# main.net
KiCad netlist of a schematic drawn in EAGLE
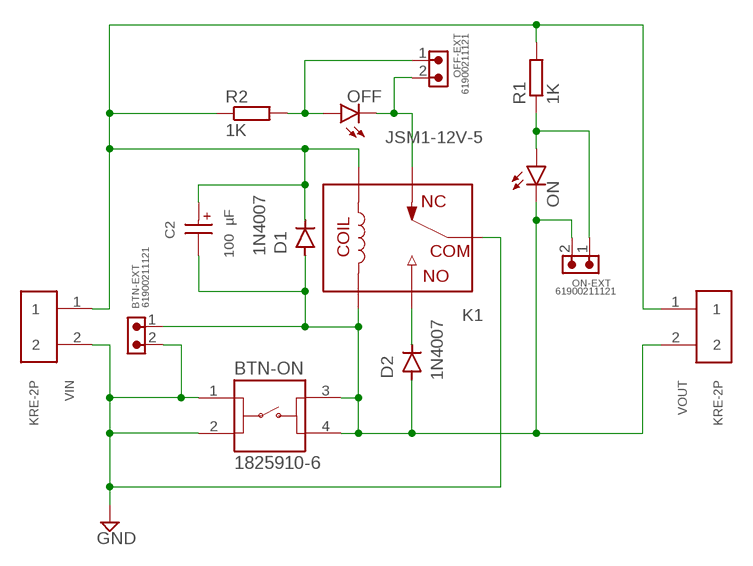
[diagram p0: schematic, sheet 1]

(export (version "E")
  (design (tool "Eeschema 10.0.6"))
  (components
    (comp (ref "BTN-EXT")
      (value "61900211121")
      (footprint "eagle-import:61900211121")
      (libsource (lib "eagle-import") (part "61900211121"))
    )
    (comp (ref "BTN-ON")
      (value "1825910-6")
      (footprint "eagle-import:1825910-6")
      (fields
        (field (name "DIGIKEY_PART_NUMBER") "450-1650-ND")
        (field (name "MANUFACTURER") "TE Connectivity ALCOSWITCH Switches")
        (field (name "CREATED_BY") " PCBLayout.com")
      )
      (libsource (lib "eagle-import") (part "1825910-6"))
    )
    (comp (ref "C2")
      (value "100 µF")
      (footprint "eagle-import:WCAP-ATLL_5X11(DXL)")
      (libsource (lib "eagle-import") (part "WCAP-ATLL_5X11_860160372011"))
    )
    (comp (ref "D1")
      (value "1N4007")
      (footprint "eagle-import:DO-41")
      (fields
        (field (name "DIGIKEY_PART_NUMBER") "1N4007MSCT-ND")
        (field (name "MANUFACTURER") "Micro Commercial Co")
        (field (name "CREATED_BY") "PCBLayout.com")
      )
      (libsource (lib "eagle-import") (part "1N4007"))
    )
    (comp (ref "D2")
      (value "1N4007")
      (footprint "eagle-import:DO-41")
      (fields
        (field (name "DIGIKEY_PART_NUMBER") "1N4007MSCT-ND")
        (field (name "MANUFACTURER") "Micro Commercial Co")
        (field (name "CREATED_BY") "PCBLayout.com")
      )
      (libsource (lib "eagle-import") (part "1N4007"))
    )
    (comp (ref "K1")
      (value "JSM1-12V-5")
      (footprint "eagle-import:JSM1-12V-5")
      (fields
        (field (name "DIGIKEY_PARTNO") "255-1240-ND")
        (field (name "MANUFACTURER") "Panasonic Electric Works")
        (field (name "CREATED_BY") "PCBLayout.com")
      )
      (libsource (lib "eagle-import") (part "JSM1-12V-5"))
    )
    (comp (ref "OFF")
      (value "LED-CIRCULAR-3MM-VERMELHO")
      (footprint "eagle-import:LED-CIR-3MM-VERMELHO")
      (libsource (lib "eagle-import") (part "LED-CIRCULAR-3MM-VERMELHO"))
    )
    (comp (ref "OFF-EXT")
      (value "61900211121")
      (footprint "eagle-import:61900211121")
      (libsource (lib "eagle-import") (part "61900211121"))
    )
    (comp (ref "ON")
      (value "LED-CIRCULAR-3MM-VERDE")
      (footprint "eagle-import:LED-CIR-3MM-VERDE")
      (libsource (lib "eagle-import") (part "LED-CIRCULAR-3MM-VERDE"))
    )
    (comp (ref "ON-EXT")
      (value "61900211121")
      (footprint "eagle-import:61900211121")
      (libsource (lib "eagle-import") (part "61900211121"))
    )
    (comp (ref "R1")
      (value "1K")
      (footprint "eagle-import:0207_7")
      (libsource (lib "eagle-import") (part "R-EU_0207/7"))
    )
    (comp (ref "R2")
      (value "1K")
      (footprint "eagle-import:0207_7")
      (libsource (lib "eagle-import") (part "R-EU_0207/7"))
    )
    (comp (ref "VIN")
      (value "KRE-2P")
      (footprint "eagle-import:KRE-2P")
      (libsource (lib "eagle-import") (part "KRE-2P"))
    )
    (comp (ref "VOUT")
      (value "KRE-2P")
      (footprint "eagle-import:KRE-2P")
      (libsource (lib "eagle-import") (part "KRE-2P"))
    )
  )
  (nets
    (net (code "1") (name "GND") (class "Default")
      (node (ref "BTN-EXT") (pin "2") (pinfunction "2_2") (pintype "passive"))
      (node (ref "BTN-ON") (pin "1") (pinfunction "1_1") (pintype "passive"))
      (node (ref "BTN-ON") (pin "2") (pinfunction "2_2") (pintype "passive"))
      (node (ref "K1") (pin "1") (pinfunction "1_1") (pintype "passive"))
      (node (ref "VIN") (pin "2") (pinfunction "2_2") (pintype "bidirectional"))
    )
    (net (code "2") (name "Net-(C2-+)") (class "Default")
      (node (ref "C2") (pin "1") (pinfunction "+_1") (pintype "passive"))
      (node (ref "D1") (pin "C") (pinfunction "C_C") (pintype "passive"))
      (node (ref "K1") (pin "5") (pinfunction "5_5") (pintype "passive"))
      (node (ref "R1") (pin "2") (pinfunction "2_2") (pintype "passive"))
      (node (ref "R2") (pin "1") (pinfunction "1_1") (pintype "passive"))
      (node (ref "VIN") (pin "1") (pinfunction "1_1") (pintype "bidirectional"))
      (node (ref "VOUT") (pin "1") (pinfunction "1_1") (pintype "bidirectional"))
    )
    (net (code "3") (name "Net-(C2--)") (class "Default")
      (node (ref "BTN-EXT") (pin "1") (pinfunction "1_1") (pintype "passive"))
      (node (ref "BTN-ON") (pin "3") (pinfunction "3_3") (pintype "passive"))
      (node (ref "BTN-ON") (pin "4") (pinfunction "4_4") (pintype "passive"))
      (node (ref "C2") (pin "2") (pinfunction "-_2") (pintype "passive"))
      (node (ref "D1") (pin "A") (pinfunction "A_A") (pintype "passive"))
      (node (ref "D2") (pin "A") (pinfunction "A_A") (pintype "passive"))
      (node (ref "K1") (pin "2") (pinfunction "2_2") (pintype "passive"))
      (node (ref "ON") (pin "K") (pinfunction "CATHODE_K") (pintype "passive"))
      (node (ref "ON-EXT") (pin "2") (pinfunction "2_2") (pintype "passive"))
      (node (ref "VOUT") (pin "2") (pinfunction "2_2") (pintype "bidirectional"))
    )
    (net (code "4") (name "Net-(D2-PadC)") (class "Default")
      (node (ref "D2") (pin "C") (pinfunction "C_C") (pintype "passive"))
      (node (ref "K1") (pin "3") (pinfunction "3_3") (pintype "passive"))
    )
    (net (code "5") (name "Net-(OFF-ANODE)") (class "Default")
      (node (ref "OFF") (pin "A") (pinfunction "ANODE_A") (pintype "passive"))
      (node (ref "OFF-EXT") (pin "1") (pinfunction "1_1") (pintype "passive"))
      (node (ref "R2") (pin "2") (pinfunction "2_2") (pintype "passive"))
    )
    (net (code "6") (name "Net-(OFF-CATHODE)") (class "Default")
      (node (ref "K1") (pin "4") (pinfunction "4_4") (pintype "passive"))
      (node (ref "OFF") (pin "K") (pinfunction "CATHODE_K") (pintype "passive"))
      (node (ref "OFF-EXT") (pin "2") (pinfunction "2_2") (pintype "passive"))
    )
    (net (code "7") (name "Net-(ON-ANODE)") (class "Default")
      (node (ref "ON") (pin "A") (pinfunction "ANODE_A") (pintype "passive"))
      (node (ref "ON-EXT") (pin "1") (pinfunction "1_1") (pintype "passive"))
      (node (ref "R1") (pin "1") (pinfunction "1_1") (pintype "passive"))
    )
  )
)
